# Core_Board.net
KiCad netlist of a schematic drawn in Altium Designer
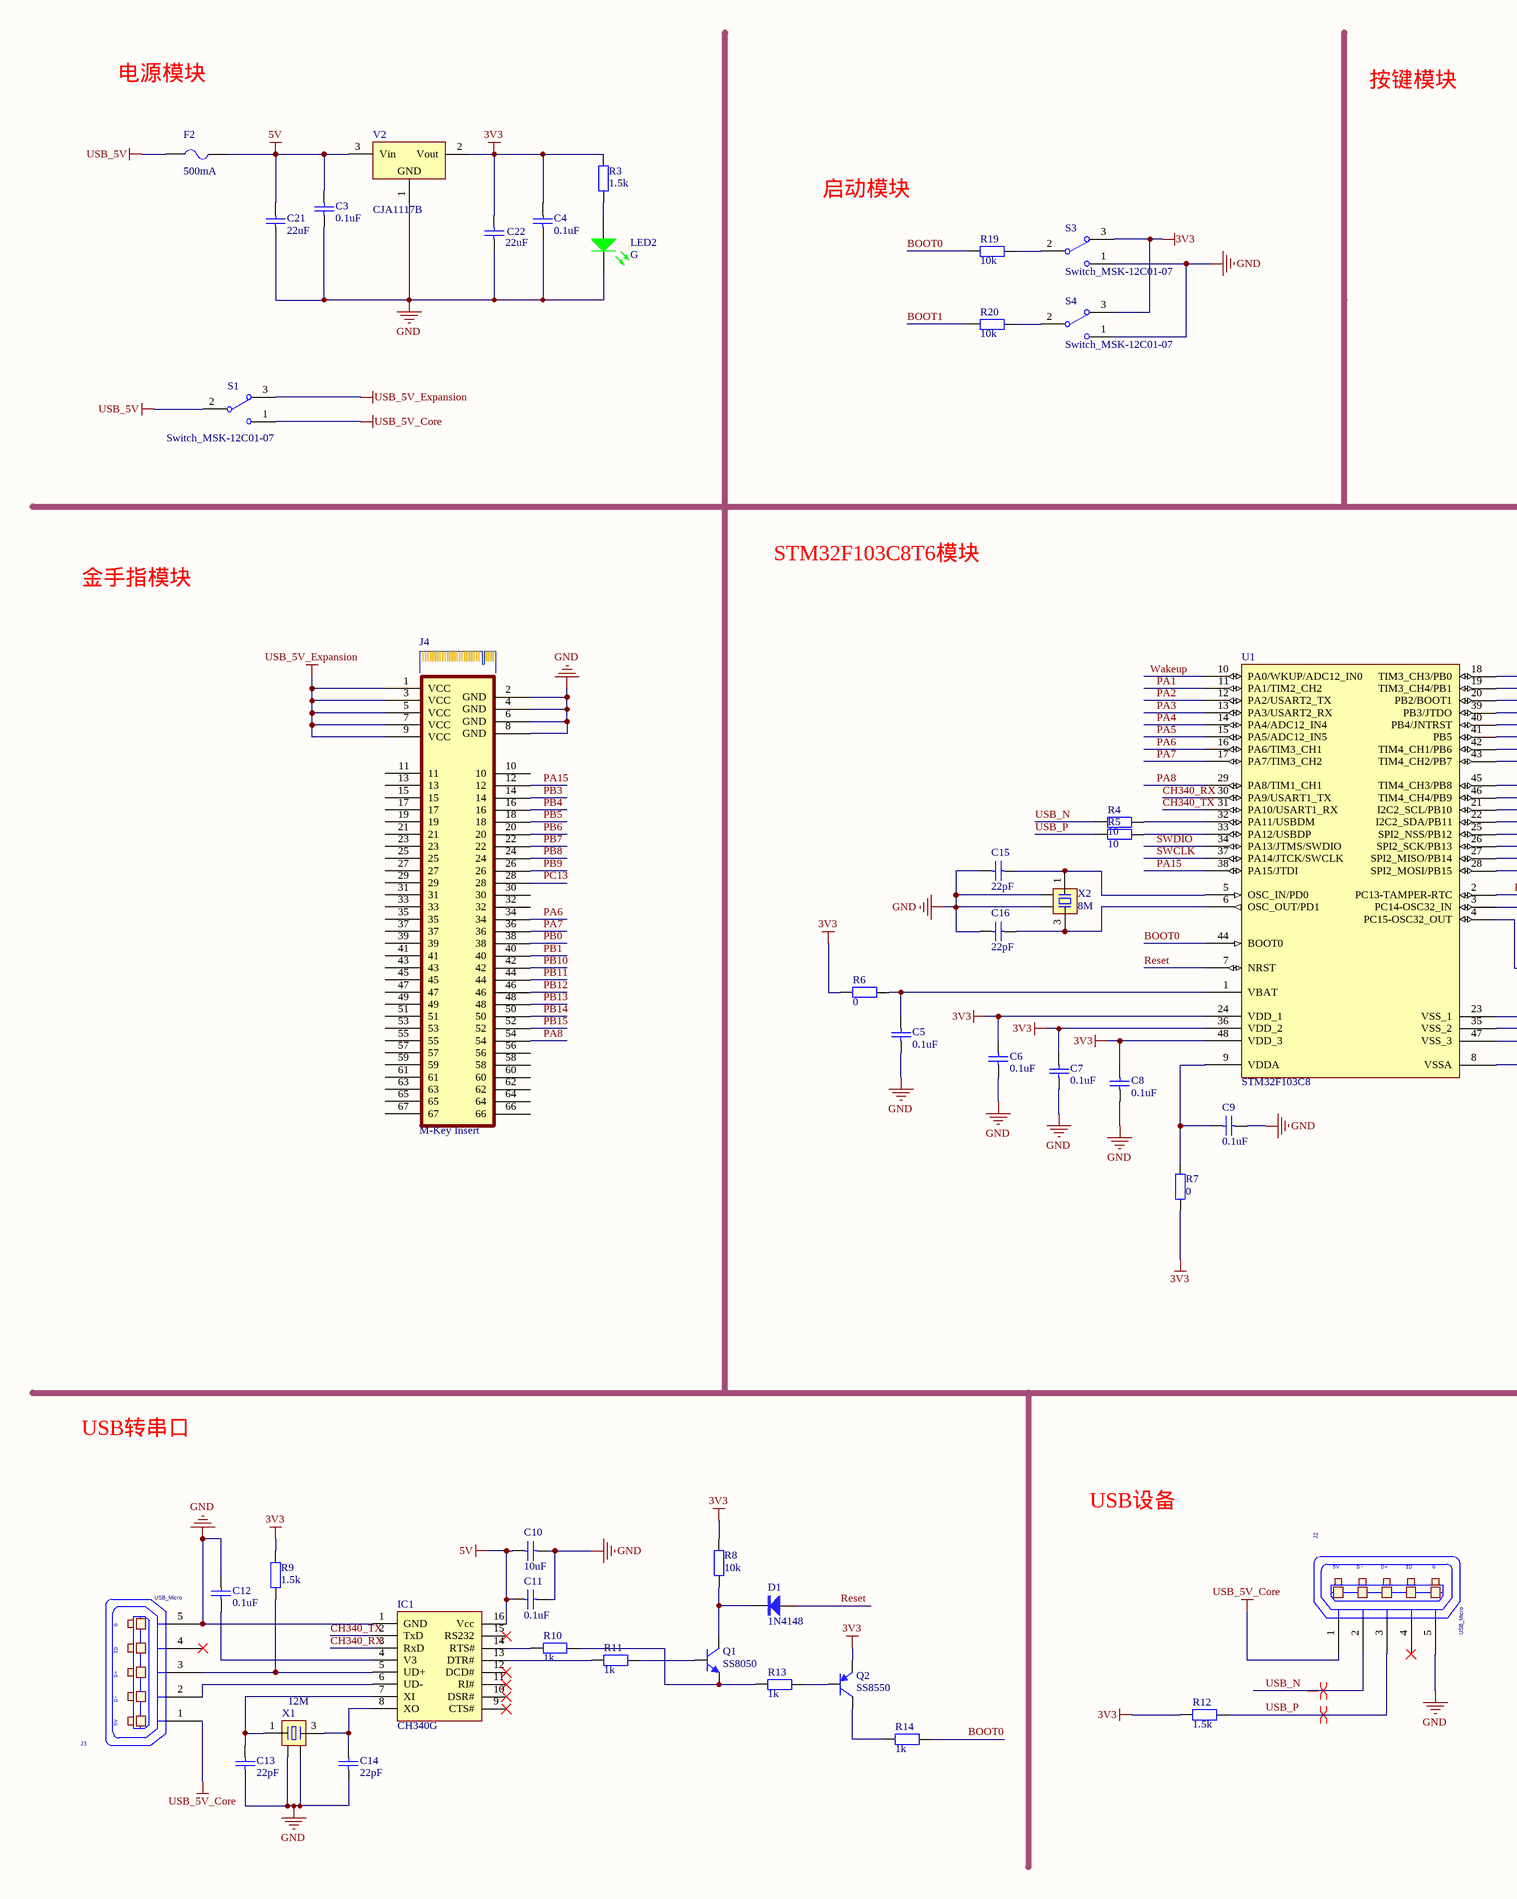
[diagram p0: Core_Board.SchDoc, left]
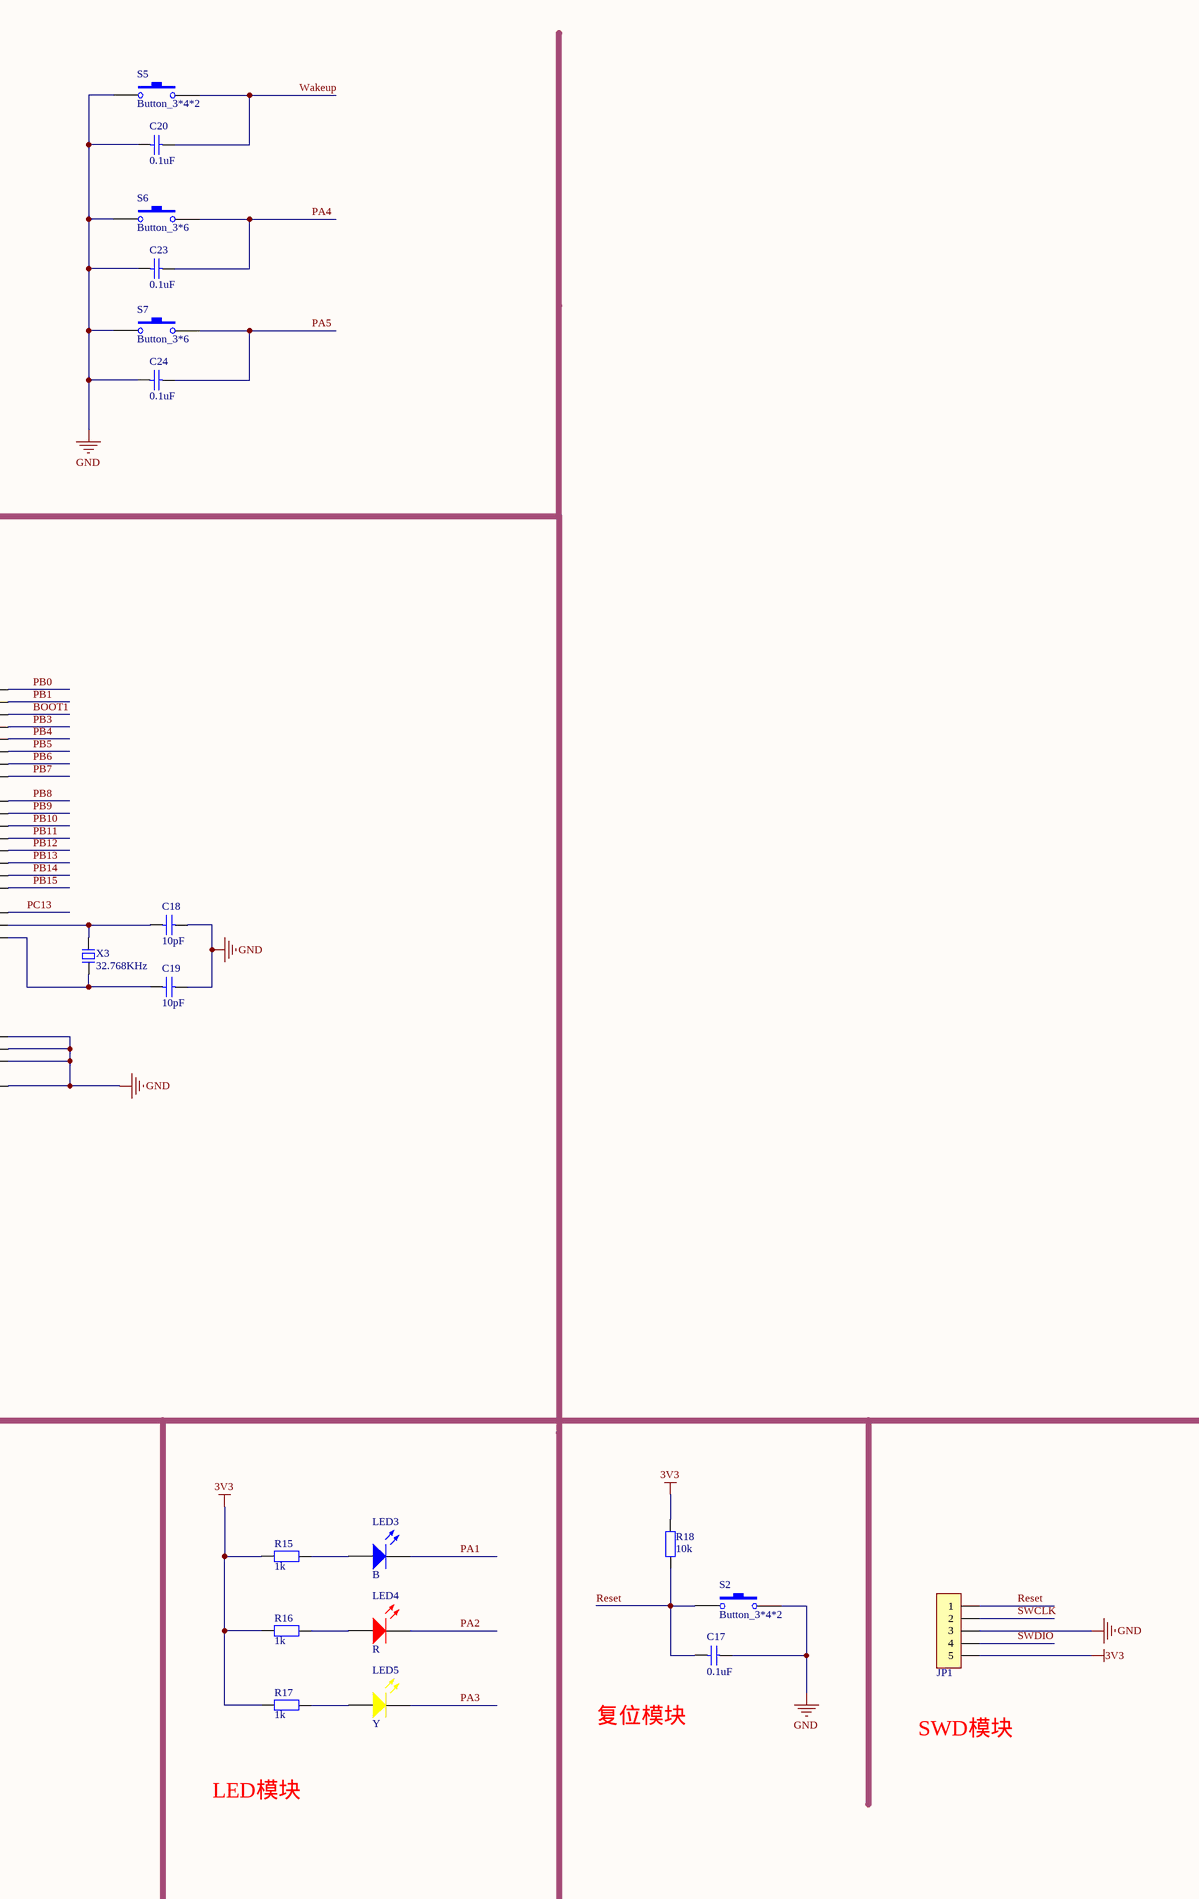
[diagram p1: Core_Board.SchDoc, right]

(export (version "E")
  (design (tool "Eeschema 10.0.6"))
  (components
    (comp (ref "C3")
      (value "0.1uF")
      (footprint "0805_C")
      (description "0805贴片电容")
      (fields (field (name "VOLTAGE") "63V") (field (name "PUBLISHER") "Altium Limited"))
      (libsource (lib "My_Intlib") (part "Cap_SMD"))
    )
    (comp (ref "C4")
      (value "0.1uF")
      (footprint "0805_C")
      (description "0805贴片电容")
      (fields (field (name "VOLTAGE") "63V") (field (name "PUBLISHER") "Altium Limited"))
      (libsource (lib "My_Intlib") (part "Cap_SMD"))
    )
    (comp (ref "C5")
      (value "0.1uF")
      (footprint "0805_C")
      (description "0805贴片电容")
      (fields (field (name "VOLTAGE") "63V") (field (name "PUBLISHER") "Altium Limited"))
      (libsource (lib "My_Intlib") (part "Cap_SMD"))
    )
    (comp (ref "C6")
      (value "0.1uF")
      (footprint "0805_C")
      (description "0805贴片电容")
      (fields (field (name "VOLTAGE") "63V") (field (name "PUBLISHER") "Altium Limited"))
      (libsource (lib "My_Intlib") (part "Cap_SMD"))
    )
    (comp (ref "C7")
      (value "0.1uF")
      (footprint "0805_C")
      (description "0805贴片电容")
      (fields (field (name "VOLTAGE") "63V") (field (name "PUBLISHER") "Altium Limited"))
      (libsource (lib "My_Intlib") (part "Cap_SMD"))
    )
    (comp (ref "C8")
      (value "0.1uF")
      (footprint "0805_C")
      (description "0805贴片电容")
      (fields (field (name "VOLTAGE") "63V") (field (name "PUBLISHER") "Altium Limited"))
      (libsource (lib "My_Intlib") (part "Cap_SMD"))
    )
    (comp (ref "C9")
      (value "0.1uF")
      (footprint "0805_C")
      (description "0805贴片电容")
      (fields (field (name "VOLTAGE") "63V") (field (name "PUBLISHER") "Altium Limited"))
      (libsource (lib "My_Intlib") (part "Cap_SMD"))
    )
    (comp (ref "C10")
      (value "10uF")
      (footprint "0805_C")
      (description "0805贴片电容")
      (fields (field (name "VOLTAGE") "63V") (field (name "PUBLISHER") "Altium Limited"))
      (libsource (lib "My_Intlib") (part "Cap_SMD"))
    )
    (comp (ref "C11")
      (value "0.1uF")
      (footprint "0805_C")
      (description "0805贴片电容")
      (fields (field (name "VOLTAGE") "63V") (field (name "PUBLISHER") "Altium Limited"))
      (libsource (lib "My_Intlib") (part "Cap_SMD"))
    )
    (comp (ref "C12")
      (value "0.1uF")
      (footprint "0805_C")
      (description "0805贴片电容")
      (fields (field (name "VOLTAGE") "63V") (field (name "PUBLISHER") "Altium Limited"))
      (libsource (lib "My_Intlib") (part "Cap_SMD"))
    )
    (comp (ref "C13")
      (value "22pF")
      (footprint "0805_C")
      (description "贴片电容")
      (fields (field (name "VOLTAGE") "63V") (field (name "PUBLISHER") "Altium Limited"))
      (libsource (lib "My_Intlib") (part "Cap_SMD"))
    )
    (comp (ref "C14")
      (value "22pF")
      (footprint "0805_C")
      (description "贴片电容")
      (fields (field (name "VOLTAGE") "63V") (field (name "PUBLISHER") "Altium Limited"))
      (libsource (lib "My_Intlib") (part "Cap_SMD"))
    )
    (comp (ref "C15")
      (value "22pF")
      (footprint "0805_C")
      (description "贴片电容")
      (fields (field (name "VOLTAGE") "63V") (field (name "PUBLISHER") "Altium Limited"))
      (libsource (lib "My_Intlib") (part "Cap_SMD"))
    )
    (comp (ref "C16")
      (value "22pF")
      (footprint "0805_C")
      (description "贴片电容")
      (fields (field (name "VOLTAGE") "63V") (field (name "PUBLISHER") "Altium Limited"))
      (libsource (lib "My_Intlib") (part "Cap_SMD"))
    )
    (comp (ref "C17")
      (value "0.1uF")
      (footprint "0805_C")
      (description "0805贴片电容")
      (fields (field (name "VOLTAGE") "63V") (field (name "PUBLISHER") "Altium Limited"))
      (libsource (lib "My_Intlib") (part "Cap_SMD"))
    )
    (comp (ref "C18")
      (value "10pF")
      (footprint "0805_C")
      (description "贴片电容")
      (fields (field (name "VOLTAGE") "63V") (field (name "PUBLISHER") "Altium Limited"))
      (libsource (lib "My_Intlib") (part "Cap_SMD"))
    )
    (comp (ref "C19")
      (value "10pF")
      (footprint "0805_C")
      (description "贴片电容")
      (fields (field (name "VOLTAGE") "63V") (field (name "PUBLISHER") "Altium Limited"))
      (libsource (lib "My_Intlib") (part "Cap_SMD"))
    )
    (comp (ref "C20")
      (value "0.1uF")
      (footprint "0805_C")
      (description "0805贴片电容")
      (fields (field (name "VOLTAGE") "63V") (field (name "PUBLISHER") "Altium Limited"))
      (libsource (lib "My_Intlib") (part "Cap_SMD"))
    )
    (comp (ref "C21")
      (value "22uF")
      (footprint "0805_C")
      (description "0805贴片电容")
      (fields (field (name "VOLTAGE") "63V") (field (name "PUBLISHER") "Altium Limited"))
      (libsource (lib "My_Intlib") (part "Cap_SMD"))
    )
    (comp (ref "C22")
      (value "22uF")
      (footprint "0805_C")
      (description "0805贴片电容")
      (fields (field (name "VOLTAGE") "63V") (field (name "PUBLISHER") "Altium Limited"))
      (libsource (lib "My_Intlib") (part "Cap_SMD"))
    )
    (comp (ref "C23")
      (value "0.1uF")
      (footprint "0805_C")
      (description "0805贴片电容")
      (fields (field (name "VOLTAGE") "63V") (field (name "PUBLISHER") "Altium Limited"))
      (libsource (lib "My_Intlib") (part "Cap_SMD"))
    )
    (comp (ref "C24")
      (value "0.1uF")
      (footprint "0805_C")
      (description "0805贴片电容")
      (fields (field (name "VOLTAGE") "63V") (field (name "PUBLISHER") "Altium Limited"))
      (libsource (lib "My_Intlib") (part "Cap_SMD"))
    )
    (comp (ref "D1")
      (value "1N4148")
      (footprint "MINI_MELF (LL34)")
      (description "高速开关二极管")
      (fields (field (name "版权归属") "源创客"))
      (libsource (lib "My_Intlib") (part "1N4148"))
    )
    (comp (ref "F2")
      (value "500mA")
      (footprint "FU 1210")
      (description "贴片保险丝")
      (fields (field (name "版权归属") "源创客"))
      (libsource (lib "My_Intlib") (part "FU"))
    )
    (comp (ref "IC1")
      (value "CH340G")
      (footprint "SOP16_N")
      (description "串口转USB")
      (fields (field (name "版权归属") "源创客"))
      (libsource (lib "My_Intlib") (part "CH340G"))
    )
    (comp (ref "J2")
      (value "USB_Micro")
      (footprint "USB-MICRO")
      (libsource (lib "My_Intlib") (part "USB_Micro"))
    )
    (comp (ref "J3")
      (value "USB_Micro")
      (footprint "USB-MICRO")
      (libsource (lib "My_Intlib") (part "USB_Micro"))
    )
    (comp (ref "J4")
      (value "M-Key Insert")
      (footprint "M-Key Insert")
      (description "M.2 金手指")
      (libsource (lib "My_Intlib") (part "M-Key Insert"))
    )
    (comp (ref "JP1")
      (value "HDR-1X5")
      (footprint "XH2.54-WI-5P")
      (description "5P接插件")
      (fields (field (name "版权归属") "源创客"))
      (libsource (lib "My_Intlib") (part "Header 5"))
    )
    (comp (ref "LED2")
      (value "G")
      (footprint "LED 0805G")
      (description "绿色LED")
      (fields (field (name "PUBLISHER") "Altium Limited"))
      (libsource (lib "My_Intlib") (part "LED_G"))
    )
    (comp (ref "LED3")
      (value "B")
      (footprint "LED 0805B")
      (description "蓝色LED")
      (fields (field (name "PUBLISHER") "Altium Limited"))
      (libsource (lib "My_Intlib") (part "LED_B"))
    )
    (comp (ref "LED4")
      (value "R")
      (footprint "LED 0805R")
      (description "红色LED")
      (fields (field (name "PUBLISHER") "Altium Limited"))
      (libsource (lib "My_Intlib") (part "LED_R"))
    )
    (comp (ref "LED5")
      (value "Y")
      (footprint "LED 0805Y")
      (description "黄色LED")
      (fields (field (name "PUBLISHER") "Altium Limited"))
      (libsource (lib "My_Intlib") (part "LED_Y"))
    )
    (comp (ref "Q1")
      (value "SS8050")
      (footprint "SOT23-3N")
      (description "高频放大-NPN型")
      (fields (field (name "版权归属") "源创客"))
      (libsource (lib "My_Intlib") (part "8050-SMD"))
    )
    (comp (ref "Q2")
      (value "SS8550")
      (footprint "SOT23-3N")
      (description "高频放大-PNP型")
      (fields (field (name "版权归属") "源创客"))
      (libsource (lib "My_Intlib") (part "8550-SMD"))
    )
    (comp (ref "R3")
      (value "1.5k")
      (footprint "0805_R")
      (description "0805贴片电阻")
      (fields (field (name "PUBLISHER") "Altium Limited"))
      (libsource (lib "") (part "Res_SMD_1"))
    )
    (comp (ref "R4")
      (value "10")
      (footprint "0805_R")
      (description "0805贴片电阻")
      (fields (field (name "PUBLISHER") "Altium Limited"))
      (libsource (lib "My_Intlib") (part "Res_SMD"))
    )
    (comp (ref "R5")
      (value "10")
      (footprint "0805_R")
      (description "0805贴片电阻")
      (fields (field (name "PUBLISHER") "Altium Limited"))
      (libsource (lib "My_Intlib") (part "Res_SMD"))
    )
    (comp (ref "R6")
      (value "0")
      (footprint "0805_R")
      (description "0805贴片电阻")
      (fields (field (name "PUBLISHER") "Altium Limited"))
      (libsource (lib "My_Intlib") (part "Res_SMD"))
    )
    (comp (ref "R7")
      (value "0")
      (footprint "0805_R")
      (description "0805贴片电阻")
      (fields (field (name "PUBLISHER") "Altium Limited"))
      (libsource (lib "") (part "Res_SMD_1"))
    )
    (comp (ref "R8")
      (value "10k")
      (footprint "0805_R")
      (description "0805贴片电阻")
      (fields (field (name "PUBLISHER") "Altium Limited"))
      (libsource (lib "") (part "Res_SMD_1"))
    )
    (comp (ref "R9")
      (value "1.5k")
      (footprint "0805_R")
      (description "0805贴片电阻")
      (fields (field (name "PUBLISHER") "Altium Limited"))
      (libsource (lib "") (part "Res_SMD_2"))
    )
    (comp (ref "R10")
      (value "1k")
      (footprint "0805_R")
      (description "0805贴片电阻")
      (fields (field (name "PUBLISHER") "Altium Limited"))
      (libsource (lib "My_Intlib") (part "Res_SMD"))
    )
    (comp (ref "R11")
      (value "1k")
      (footprint "0805_R")
      (description "0805贴片电阻")
      (fields (field (name "PUBLISHER") "Altium Limited"))
      (libsource (lib "My_Intlib") (part "Res_SMD"))
    )
    (comp (ref "R12")
      (value "1.5k")
      (footprint "0805_R")
      (description "0805贴片电阻")
      (fields (field (name "PUBLISHER") "Altium Limited"))
      (libsource (lib "My_Intlib") (part "Res_SMD"))
    )
    (comp (ref "R13")
      (value "1k")
      (footprint "0805_R")
      (description "0805贴片电阻")
      (fields (field (name "PUBLISHER") "Altium Limited"))
      (libsource (lib "My_Intlib") (part "Res_SMD"))
    )
    (comp (ref "R14")
      (value "1k")
      (footprint "0805_R")
      (description "0805贴片电阻")
      (fields (field (name "PUBLISHER") "Altium Limited"))
      (libsource (lib "") (part "Res_SMD_3"))
    )
    (comp (ref "R15")
      (value "1k")
      (footprint "0805_R")
      (description "0805贴片电阻")
      (fields (field (name "PUBLISHER") "Altium Limited"))
      (libsource (lib "My_Intlib") (part "Res_SMD"))
    )
    (comp (ref "R16")
      (value "1k")
      (footprint "0805_R")
      (description "0805贴片电阻")
      (fields (field (name "PUBLISHER") "Altium Limited"))
      (libsource (lib "My_Intlib") (part "Res_SMD"))
    )
    (comp (ref "R17")
      (value "1k")
      (footprint "0805_R")
      (description "0805贴片电阻")
      (fields (field (name "PUBLISHER") "Altium Limited"))
      (libsource (lib "My_Intlib") (part "Res_SMD"))
    )
    (comp (ref "R18")
      (value "10k")
      (footprint "0805_R")
      (description "0805贴片电阻")
      (fields (field (name "PUBLISHER") "Altium Limited"))
      (libsource (lib "") (part "Res_SMD_2"))
    )
    (comp (ref "R19")
      (value "10k")
      (footprint "0805_R")
      (description "0805贴片电阻")
      (fields (field (name "PUBLISHER") "Altium Limited"))
      (libsource (lib "My_Intlib") (part "Res_SMD"))
    )
    (comp (ref "R20")
      (value "10k")
      (footprint "0805_R")
      (description "0805贴片电阻")
      (fields (field (name "PUBLISHER") "Altium Limited"))
      (libsource (lib "My_Intlib") (part "Res_SMD"))
    )
    (comp (ref "S1")
      (value "Switch_MSK-12C01-07")
      (footprint "MSK-12C01-07")
      (libsource (lib "My_Intlib") (part "Switch_MSK-12C01-07"))
    )
    (comp (ref "S2")
      (value "Button_3*4*2")
      (footprint "TSW SMD-3*4*2")
      (fields (field (name "PUBLISHER") "Altium Limited"))
      (libsource (lib "My_Intlib") (part "Button_3*4*2"))
    )
    (comp (ref "S3")
      (value "Switch_MSK-12C01-07")
      (footprint "MSK-12C01-07")
      (libsource (lib "My_Intlib") (part "Switch_MSK-12C01-07"))
    )
    (comp (ref "S4")
      (value "Switch_MSK-12C01-07")
      (footprint "MSK-12C01-07")
      (libsource (lib "My_Intlib") (part "Switch_MSK-12C01-07"))
    )
    (comp (ref "S5")
      (value "Button_3*4*2")
      (footprint "TSW SMD-3*4*2")
      (fields (field (name "PUBLISHER") "Altium Limited"))
      (libsource (lib "My_Intlib") (part "Button_3*4*2"))
    )
    (comp (ref "S6")
      (value "Button_3*6")
      (footprint "TSW SMD-3*6*4.3_V")
      (description "3mm*4mm*按钮长度待定")
      (fields (field (name "PUBLISHER") "Altium Limited"))
      (libsource (lib "My_Intlib") (part "Button_3*6"))
    )
    (comp (ref "S7")
      (value "Button_3*6")
      (footprint "TSW SMD-3*6*4.3_V")
      (description "3mm*4mm*按钮长度待定")
      (fields (field (name "PUBLISHER") "Altium Limited"))
      (libsource (lib "My_Intlib") (part "Button_3*6"))
    )
    (comp (ref "U1")
      (value "STM32F103C8")
      (footprint "LQFP48 7X7_N")
      (description "Flaah:64/RAM:20/IO:36")
      (libsource (lib "My_Intlib") (part "STM32F103C8"))
    )
    (comp (ref "V2")
      (value "CJA1117B")
      (footprint "SOT89_N")
      (description "三端稳压芯片")
      (fields (field (name "版权归属") "源创客"))
      (libsource (lib "My_Intlib") (part "CJA1117B"))
    )
    (comp (ref "X1")
      (value "12M")
      (footprint "OSC 3225-4P")
      (description "4脚无源晶振")
      (fields (field (name "版权归属") "源创客"))
      (libsource (lib "My_Intlib") (part "XTAL-4P"))
    )
    (comp (ref "X2")
      (value "8M")
      (footprint "OSC 3225-4P")
      (description "4脚无源晶振")
      (fields (field (name "版权归属") "源创客"))
      (libsource (lib "") (part "XTAL-4P_1"))
    )
    (comp (ref "X3")
      (value "32.768KHz")
      (footprint "OSC 3215-2P")
      (description "2脚无源脚晶振")
      (fields (field (name "版权归属") "源创客"))
      (libsource (lib "10.1 - 保险丝-晶振") (part "XTAL-2P"))
    )
  )
  (nets
    (net (code "1") (name "/BOOT0") (class "Default")
      (node (ref "R14") (pin "1") (pinfunction "1_1") (pintype "passive"))
      (node (ref "R19") (pin "1") (pinfunction "1_1") (pintype "passive"))
      (node (ref "U1") (pin "44") (pinfunction "BOOT0_44") (pintype "input"))
    )
    (net (code "2") (name "/BOOT1") (class "Default")
      (node (ref "R20") (pin "1") (pinfunction "1_1") (pintype "passive"))
      (node (ref "U1") (pin "20") (pinfunction "PB2/BOOT1_20") (pintype "bidirectional"))
    )
    (net (code "3") (name "/CH340_RX") (class "Default")
      (node (ref "IC1") (pin "3") (pinfunction "RxD_3") (pintype "passive"))
      (node (ref "U1") (pin "30") (pinfunction "PA9/USART1_TX_30") (pintype "bidirectional"))
    )
    (net (code "4") (name "/CH340_TX") (class "Default")
      (node (ref "IC1") (pin "2") (pinfunction "TxD_2") (pintype "passive"))
      (node (ref "U1") (pin "31") (pinfunction "PA10/USART1_RX_31") (pintype "bidirectional"))
    )
    (net (code "5") (name "/PA1") (class "Default")
      (node (ref "LED3") (pin "2") (pinfunction "K_2") (pintype "passive"))
      (node (ref "U1") (pin "11") (pinfunction "PA1/TIM2_CH2_11") (pintype "bidirectional"))
    )
    (net (code "6") (name "/PA2") (class "Default")
      (node (ref "LED4") (pin "2") (pinfunction "K_2") (pintype "passive"))
      (node (ref "U1") (pin "12") (pinfunction "PA2/USART2_TX_12") (pintype "bidirectional"))
    )
    (net (code "7") (name "/PA3") (class "Default")
      (node (ref "LED5") (pin "2") (pinfunction "K_2") (pintype "passive"))
      (node (ref "U1") (pin "13") (pinfunction "PA3/USART2_RX_13") (pintype "bidirectional"))
    )
    (net (code "8") (name "/PA4") (class "Default")
      (node (ref "C23") (pin "2") (pinfunction "2_2") (pintype "passive"))
      (node (ref "S6") (pin "2") (pinfunction "2_2") (pintype "passive"))
      (node (ref "U1") (pin "14") (pinfunction "PA4/ADC12_IN4_14") (pintype "bidirectional"))
    )
    (net (code "9") (name "/PA5") (class "Default")
      (node (ref "C24") (pin "2") (pinfunction "2_2") (pintype "passive"))
      (node (ref "S7") (pin "2") (pinfunction "2_2") (pintype "passive"))
      (node (ref "U1") (pin "15") (pinfunction "PA5/ADC12_IN5_15") (pintype "bidirectional"))
    )
    (net (code "10") (name "/PA6") (class "Default")
      (node (ref "J4") (pin "34") (pinfunction "34_34") (pintype "passive"))
      (node (ref "U1") (pin "16") (pinfunction "PA6/TIM3_CH1_16") (pintype "bidirectional"))
    )
    (net (code "11") (name "/PA7") (class "Default")
      (node (ref "J4") (pin "36") (pinfunction "36_36") (pintype "passive"))
      (node (ref "U1") (pin "17") (pinfunction "PA7/TIM3_CH2_17") (pintype "bidirectional"))
    )
    (net (code "12") (name "/PA8") (class "Default")
      (node (ref "J4") (pin "54") (pinfunction "54_54") (pintype "passive"))
      (node (ref "U1") (pin "29") (pinfunction "PA8/TIM1_CH1_29") (pintype "bidirectional"))
    )
    (net (code "13") (name "/PA15") (class "Default")
      (node (ref "J4") (pin "12") (pinfunction "12_12") (pintype "passive"))
      (node (ref "U1") (pin "38") (pinfunction "PA15/JTDI_38") (pintype "bidirectional"))
    )
    (net (code "14") (name "/PB0") (class "Default")
      (node (ref "J4") (pin "38") (pinfunction "38_38") (pintype "passive"))
      (node (ref "U1") (pin "18") (pinfunction "TIM3_CH3/PB0_18") (pintype "bidirectional"))
    )
    (net (code "15") (name "/PB1") (class "Default")
      (node (ref "J4") (pin "40") (pinfunction "40_40") (pintype "passive"))
      (node (ref "U1") (pin "19") (pinfunction "TIM3_CH4/PB1_19") (pintype "bidirectional"))
    )
    (net (code "16") (name "/PB3") (class "Default")
      (node (ref "J4") (pin "14") (pinfunction "14_14") (pintype "passive"))
      (node (ref "U1") (pin "39") (pinfunction "PB3/JTDO_39") (pintype "bidirectional"))
    )
    (net (code "17") (name "/PB4") (class "Default")
      (node (ref "J4") (pin "16") (pinfunction "16_16") (pintype "passive"))
      (node (ref "U1") (pin "40") (pinfunction "PB4/JNTRST_40") (pintype "bidirectional"))
    )
    (net (code "18") (name "/PB5") (class "Default")
      (node (ref "J4") (pin "18") (pinfunction "18_18") (pintype "passive"))
      (node (ref "U1") (pin "41") (pinfunction "PB5_41") (pintype "bidirectional"))
    )
    (net (code "19") (name "/PB6") (class "Default")
      (node (ref "J4") (pin "20") (pinfunction "20_20") (pintype "passive"))
      (node (ref "U1") (pin "42") (pinfunction "TIM4_CH1/PB6_42") (pintype "bidirectional"))
    )
    (net (code "20") (name "/PB7") (class "Default")
      (node (ref "J4") (pin "22") (pinfunction "22_22") (pintype "passive"))
      (node (ref "U1") (pin "43") (pinfunction "TIM4_CH2/PB7_43") (pintype "bidirectional"))
    )
    (net (code "21") (name "/PB8") (class "Default")
      (node (ref "J4") (pin "24") (pinfunction "24_24") (pintype "passive"))
      (node (ref "U1") (pin "45") (pinfunction "TIM4_CH3/PB8_45") (pintype "bidirectional"))
    )
    (net (code "22") (name "/PB9") (class "Default")
      (node (ref "J4") (pin "26") (pinfunction "26_26") (pintype "passive"))
      (node (ref "U1") (pin "46") (pinfunction "TIM4_CH4/PB9_46") (pintype "bidirectional"))
    )
    (net (code "23") (name "/PB10") (class "Default")
      (node (ref "J4") (pin "42") (pinfunction "42_42") (pintype "passive"))
      (node (ref "U1") (pin "21") (pinfunction "I2C2_SCL/PB10_21") (pintype "bidirectional"))
    )
    (net (code "24") (name "/PB11") (class "Default")
      (node (ref "J4") (pin "44") (pinfunction "44_44") (pintype "passive"))
      (node (ref "U1") (pin "22") (pinfunction "I2C2_SDA/PB11_22") (pintype "bidirectional"))
    )
    (net (code "25") (name "/PB12") (class "Default")
      (node (ref "J4") (pin "46") (pinfunction "46_46") (pintype "passive"))
      (node (ref "U1") (pin "25") (pinfunction "SPI2_NSS/PB12_25") (pintype "bidirectional"))
    )
    (net (code "26") (name "/PB13") (class "Default")
      (node (ref "J4") (pin "48") (pinfunction "48_48") (pintype "passive"))
      (node (ref "U1") (pin "26") (pinfunction "SPI2_SCK/PB13_26") (pintype "bidirectional"))
    )
    (net (code "27") (name "/PB14") (class "Default")
      (node (ref "J4") (pin "50") (pinfunction "50_50") (pintype "passive"))
      (node (ref "U1") (pin "27") (pinfunction "SPI2_MISO/PB14_27") (pintype "bidirectional"))
    )
    (net (code "28") (name "/PB15") (class "Default")
      (node (ref "J4") (pin "52") (pinfunction "52_52") (pintype "passive"))
      (node (ref "U1") (pin "28") (pinfunction "SPI2_MOSI/PB15_28") (pintype "bidirectional"))
    )
    (net (code "29") (name "/PC13") (class "Default")
      (node (ref "J4") (pin "28") (pinfunction "28_28") (pintype "passive"))
      (node (ref "U1") (pin "2") (pinfunction "PC13-TAMPER-RTC_2") (pintype "bidirectional"))
    )
    (net (code "30") (name "/Reset") (class "Default")
      (node (ref "C17") (pin "2") (pinfunction "2_2") (pintype "passive"))
      (node (ref "D1") (pin "1") (pinfunction "A_1") (pintype "passive"))
      (node (ref "JP1") (pin "1") (pinfunction "1_1") (pintype "passive"))
      (node (ref "R18") (pin "2") (pinfunction "2_2") (pintype "passive"))
      (node (ref "S2") (pin "1") (pinfunction "1_1") (pintype "passive"))
      (node (ref "U1") (pin "7") (pinfunction "NRST_7") (pintype "bidirectional"))
    )
    (net (code "31") (name "/SWCLK") (class "Default")
      (node (ref "JP1") (pin "2") (pinfunction "2_2") (pintype "passive"))
      (node (ref "U1") (pin "37") (pinfunction "PA14/JTCK/SWCLK_37") (pintype "bidirectional"))
    )
    (net (code "32") (name "/SWDIO") (class "Default")
      (node (ref "JP1") (pin "4") (pinfunction "4_4") (pintype "passive"))
      (node (ref "U1") (pin "34") (pinfunction "PA13/JTMS/SWDIO_34") (pintype "bidirectional"))
    )
    (net (code "33") (name "/USB_N") (class "Default")
      (node (ref "J2") (pin "2") (pinfunction "P2_2") (pintype "passive"))
      (node (ref "R4") (pin "1") (pinfunction "1_1") (pintype "passive"))
    )
    (net (code "34") (name "/USB_P") (class "Default")
      (node (ref "J2") (pin "3") (pinfunction "P3_3") (pintype "passive"))
      (node (ref "R12") (pin "2") (pinfunction "2_2") (pintype "passive"))
      (node (ref "R5") (pin "1") (pinfunction "1_1") (pintype "passive"))
    )
    (net (code "35") (name "/Wakeup") (class "Default")
      (node (ref "C20") (pin "2") (pinfunction "2_2") (pintype "passive"))
      (node (ref "S5") (pin "2") (pinfunction "2_2") (pintype "passive"))
      (node (ref "U1") (pin "10") (pinfunction "PA0/WKUP/ADC12_IN0_10") (pintype "bidirectional"))
    )
    (net (code "36") (name "3V3") (class "Default")
      (node (ref "C22") (pin "2") (pinfunction "2_2") (pintype "passive"))
      (node (ref "C4") (pin "2") (pinfunction "2_2") (pintype "passive"))
      (node (ref "C6") (pin "2") (pinfunction "2_2") (pintype "passive"))
      (node (ref "C7") (pin "2") (pinfunction "2_2") (pintype "passive"))
      (node (ref "C8") (pin "2") (pinfunction "2_2") (pintype "passive"))
      (node (ref "JP1") (pin "5") (pinfunction "5_5") (pintype "passive"))
      (node (ref "Q2") (pin "2") (pinfunction "E_2") (pintype "passive"))
      (node (ref "R12") (pin "1") (pinfunction "1_1") (pintype "passive"))
      (node (ref "R15") (pin "1") (pinfunction "1_1") (pintype "passive"))
      (node (ref "R16") (pin "1") (pinfunction "1_1") (pintype "passive"))
      (node (ref "R17") (pin "1") (pinfunction "1_1") (pintype "passive"))
      (node (ref "R18") (pin "1") (pinfunction "1_1") (pintype "passive"))
      (node (ref "R3") (pin "2") (pinfunction "2_2") (pintype "passive"))
      (node (ref "R6") (pin "1") (pinfunction "1_1") (pintype "passive"))
      (node (ref "R7") (pin "1") (pinfunction "1_1") (pintype "passive"))
      (node (ref "R8") (pin "2") (pinfunction "2_2") (pintype "passive"))
      (node (ref "R9") (pin "1") (pinfunction "1_1") (pintype "passive"))
      (node (ref "S3") (pin "3") (pinfunction "3_3") (pintype "passive"))
      (node (ref "S4") (pin "3") (pinfunction "3_3") (pintype "passive"))
      (node (ref "U1") (pin "24") (pinfunction "VDD_1_24") (pintype "power_in"))
      (node (ref "U1") (pin "36") (pinfunction "VDD_2_36") (pintype "power_in"))
      (node (ref "U1") (pin "48") (pinfunction "VDD_3_48") (pintype "power_in"))
      (node (ref "V2") (pin "2") (pinfunction "Vout_2") (pintype "passive"))
    )
    (net (code "37") (name "5V") (class "Default")
      (node (ref "C10") (pin "2") (pinfunction "2_2") (pintype "passive"))
      (node (ref "C11") (pin "2") (pinfunction "2_2") (pintype "passive"))
      (node (ref "C21") (pin "2") (pinfunction "2_2") (pintype "passive"))
      (node (ref "C3") (pin "2") (pinfunction "2_2") (pintype "passive"))
      (node (ref "F2") (pin "2") (pinfunction "2_2") (pintype "passive"))
      (node (ref "IC1") (pin "16") (pinfunction "Vcc_16") (pintype "passive"))
      (node (ref "V2") (pin "3") (pinfunction "Vin_3") (pintype "passive"))
    )
    (net (code "38") (name "GND") (class "Default")
      (node (ref "C10") (pin "1") (pinfunction "1_1") (pintype "passive"))
      (node (ref "C11") (pin "1") (pinfunction "1_1") (pintype "passive"))
      (node (ref "C12") (pin "2") (pinfunction "2_2") (pintype "passive"))
      (node (ref "C13") (pin "1") (pinfunction "1_1") (pintype "passive"))
      (node (ref "C14") (pin "1") (pinfunction "1_1") (pintype "passive"))
      (node (ref "C15") (pin "2") (pinfunction "2_2") (pintype "passive"))
      (node (ref "C16") (pin "2") (pinfunction "2_2") (pintype "passive"))
      (node (ref "C17") (pin "1") (pinfunction "1_1") (pintype "passive"))
      (node (ref "C18") (pin "2") (pinfunction "2_2") (pintype "passive"))
      (node (ref "C19") (pin "2") (pinfunction "2_2") (pintype "passive"))
      (node (ref "C20") (pin "1") (pinfunction "1_1") (pintype "passive"))
      (node (ref "C21") (pin "1") (pinfunction "1_1") (pintype "passive"))
      (node (ref "C22") (pin "1") (pinfunction "1_1") (pintype "passive"))
      (node (ref "C23") (pin "1") (pinfunction "1_1") (pintype "passive"))
      (node (ref "C24") (pin "1") (pinfunction "1_1") (pintype "passive"))
      (node (ref "C3") (pin "1") (pinfunction "1_1") (pintype "passive"))
      (node (ref "C4") (pin "1") (pinfunction "1_1") (pintype "passive"))
      (node (ref "C5") (pin "1") (pinfunction "1_1") (pintype "passive"))
      (node (ref "C6") (pin "1") (pinfunction "1_1") (pintype "passive"))
      (node (ref "C7") (pin "1") (pinfunction "1_1") (pintype "passive"))
      (node (ref "C8") (pin "1") (pinfunction "1_1") (pintype "passive"))
      (node (ref "C9") (pin "1") (pinfunction "1_1") (pintype "passive"))
      (node (ref "IC1") (pin "1") (pinfunction "GND_1") (pintype "passive"))
      (node (ref "J2") (pin "5") (pinfunction "P5_5") (pintype "passive"))
      (node (ref "J3") (pin "5") (pinfunction "P5_5") (pintype "passive"))
      (node (ref "J4") (pin "2") (pinfunction "GND_2") (pintype "passive"))
      (node (ref "J4") (pin "4") (pinfunction "GND_4") (pintype "passive"))
      (node (ref "J4") (pin "6") (pinfunction "GND_6") (pintype "passive"))
      (node (ref "J4") (pin "8") (pinfunction "GND_8") (pintype "passive"))
      (node (ref "JP1") (pin "3") (pinfunction "3_3") (pintype "passive"))
      (node (ref "LED2") (pin "2") (pinfunction "K_2") (pintype "passive"))
      (node (ref "S2") (pin "2") (pinfunction "2_2") (pintype "passive"))
      (node (ref "S3") (pin "1") (pinfunction "1_1") (pintype "passive"))
      (node (ref "S4") (pin "1") (pinfunction "1_1") (pintype "passive"))
      (node (ref "S5") (pin "1") (pinfunction "1_1") (pintype "passive"))
      (node (ref "S6") (pin "1") (pinfunction "1_1") (pintype "passive"))
      (node (ref "S7") (pin "1") (pinfunction "1_1") (pintype "passive"))
      (node (ref "U1") (pin "23") (pinfunction "VSS_1_23") (pintype "power_in"))
      (node (ref "U1") (pin "35") (pinfunction "VSS_2_35") (pintype "power_in"))
      (node (ref "U1") (pin "47") (pinfunction "VSS_3_47") (pintype "power_in"))
      (node (ref "U1") (pin "8") (pinfunction "VSSA_8") (pintype "power_in"))
      (node (ref "V2") (pin "1") (pinfunction "GND_1") (pintype "passive"))
      (node (ref "X1") (pin "2") (pinfunction "2_2") (pintype "passive"))
      (node (ref "X1") (pin "4") (pinfunction "4_4") (pintype "passive"))
      (node (ref "X2") (pin "2") (pinfunction "2_2") (pintype "passive"))
      (node (ref "X2") (pin "4") (pinfunction "4_4") (pintype "passive"))
    )
    (net (code "39") (name "Net-(D1-K)") (class "Default")
      (node (ref "D1") (pin "2") (pinfunction "K_2") (pintype "passive"))
      (node (ref "Q1") (pin "3") (pinfunction "C_3") (pintype "passive"))
      (node (ref "R8") (pin "1") (pinfunction "1_1") (pintype "passive"))
    )
    (net (code "40") (name "Net-(IC1-DTR#)") (class "Default")
      (node (ref "IC1") (pin "13") (pinfunction "DTR#_13") (pintype "passive"))
      (node (ref "R11") (pin "1") (pinfunction "1_1") (pintype "passive"))
    )
    (net (code "41") (name "Net-(IC1-RTS#)") (class "Default")
      (node (ref "IC1") (pin "14") (pinfunction "RTS#_14") (pintype "passive"))
      (node (ref "R10") (pin "1") (pinfunction "1_1") (pintype "passive"))
    )
    (net (code "42") (name "Net-(IC1-UD+)") (class "Default")
      (node (ref "IC1") (pin "5") (pinfunction "UD+_5") (pintype "passive"))
      (node (ref "J3") (pin "3") (pinfunction "P3_3") (pintype "passive"))
      (node (ref "R9") (pin "2") (pinfunction "2_2") (pintype "passive"))
    )
    (net (code "43") (name "Net-(IC1-UD-)") (class "Default")
      (node (ref "IC1") (pin "6") (pinfunction "UD-_6") (pintype "passive"))
      (node (ref "J3") (pin "2") (pinfunction "P2_2") (pintype "passive"))
    )
    (net (code "44") (name "Net-(IC1-V3)") (class "Default")
      (node (ref "C12") (pin "1") (pinfunction "1_1") (pintype "passive"))
      (node (ref "IC1") (pin "4") (pinfunction "V3_4") (pintype "passive"))
    )
    (net (code "45") (name "Net-(IC1-XI)") (class "Default")
      (node (ref "C13") (pin "2") (pinfunction "2_2") (pintype "passive"))
      (node (ref "IC1") (pin "7") (pinfunction "XI_7") (pintype "passive"))
      (node (ref "X1") (pin "1") (pinfunction "1_1") (pintype "passive"))
    )
    (net (code "46") (name "Net-(IC1-XO)") (class "Default")
      (node (ref "C14") (pin "2") (pinfunction "2_2") (pintype "passive"))
      (node (ref "IC1") (pin "8") (pinfunction "XO_8") (pintype "passive"))
      (node (ref "X1") (pin "3") (pinfunction "3_3") (pintype "passive"))
    )
    (net (code "47") (name "Net-(LED2-A)") (class "Default")
      (node (ref "LED2") (pin "1") (pinfunction "A_1") (pintype "passive"))
      (node (ref "R3") (pin "1") (pinfunction "1_1") (pintype "passive"))
    )
    (net (code "48") (name "Net-(LED3-A)") (class "Default")
      (node (ref "LED3") (pin "1") (pinfunction "A_1") (pintype "passive"))
      (node (ref "R15") (pin "2") (pinfunction "2_2") (pintype "passive"))
    )
    (net (code "49") (name "Net-(LED4-A)") (class "Default")
      (node (ref "LED4") (pin "1") (pinfunction "A_1") (pintype "passive"))
      (node (ref "R16") (pin "2") (pinfunction "2_2") (pintype "passive"))
    )
    (net (code "50") (name "Net-(LED5-A)") (class "Default")
      (node (ref "LED5") (pin "1") (pinfunction "A_1") (pintype "passive"))
      (node (ref "R17") (pin "2") (pinfunction "2_2") (pintype "passive"))
    )
    (net (code "51") (name "Net-(Q1-B)") (class "Default")
      (node (ref "Q1") (pin "1") (pinfunction "B_1") (pintype "passive"))
      (node (ref "R11") (pin "2") (pinfunction "2_2") (pintype "passive"))
    )
    (net (code "52") (name "Net-(Q1-E)") (class "Default")
      (node (ref "Q1") (pin "2") (pinfunction "E_2") (pintype "passive"))
      (node (ref "R10") (pin "2") (pinfunction "2_2") (pintype "passive"))
      (node (ref "R13") (pin "1") (pinfunction "1_1") (pintype "passive"))
    )
    (net (code "53") (name "Net-(Q2-B)") (class "Default")
      (node (ref "Q2") (pin "1") (pinfunction "B_1") (pintype "passive"))
      (node (ref "R13") (pin "2") (pinfunction "2_2") (pintype "passive"))
    )
    (net (code "54") (name "Net-(Q2-C)") (class "Default")
      (node (ref "Q2") (pin "3") (pinfunction "C_3") (pintype "passive"))
      (node (ref "R14") (pin "2") (pinfunction "2_2") (pintype "passive"))
    )
    (net (code "55") (name "Net-(R19-Pad2)") (class "Default")
      (node (ref "R19") (pin "2") (pinfunction "2_2") (pintype "passive"))
      (node (ref "S3") (pin "2") (pinfunction "2_2") (pintype "passive"))
    )
    (net (code "56") (name "Net-(R20-Pad2)") (class "Default")
      (node (ref "R20") (pin "2") (pinfunction "2_2") (pintype "passive"))
      (node (ref "S4") (pin "2") (pinfunction "2_2") (pintype "passive"))
    )
    (net (code "57") (name "Net-(U1-OSC_IN{slash}PD0)") (class "Default")
      (node (ref "C15") (pin "1") (pinfunction "1_1") (pintype "passive"))
      (node (ref "U1") (pin "5") (pinfunction "OSC_IN/PD0_5") (pintype "input"))
      (node (ref "X2") (pin "1") (pinfunction "1_1") (pintype "passive"))
    )
    (net (code "58") (name "Net-(U1-OSC_OUT{slash}PD1)") (class "Default")
      (node (ref "C16") (pin "1") (pinfunction "1_1") (pintype "passive"))
      (node (ref "U1") (pin "6") (pinfunction "OSC_OUT/PD1_6") (pintype "output"))
      (node (ref "X2") (pin "3") (pinfunction "3_3") (pintype "passive"))
    )
    (net (code "59") (name "Net-(U1-PA11{slash}USBDM)") (class "Default")
      (node (ref "R4") (pin "2") (pinfunction "2_2") (pintype "passive"))
      (node (ref "U1") (pin "32") (pinfunction "PA11/USBDM_32") (pintype "bidirectional"))
    )
    (net (code "60") (name "Net-(U1-PA12{slash}USBDP)") (class "Default")
      (node (ref "R5") (pin "2") (pinfunction "2_2") (pintype "passive"))
      (node (ref "U1") (pin "33") (pinfunction "PA12/USBDP_33") (pintype "bidirectional"))
    )
    (net (code "61") (name "Net-(U1-PC14-OSC32_IN)") (class "Default")
      (node (ref "C18") (pin "1") (pinfunction "1_1") (pintype "passive"))
      (node (ref "U1") (pin "3") (pinfunction "PC14-OSC32_IN_3") (pintype "bidirectional"))
      (node (ref "X3") (pin "2") (pinfunction "2_2") (pintype "passive"))
    )
    (net (code "62") (name "Net-(U1-PC15-OSC32_OUT)") (class "Default")
      (node (ref "C19") (pin "1") (pinfunction "1_1") (pintype "passive"))
      (node (ref "U1") (pin "4") (pinfunction "PC15-OSC32_OUT_4") (pintype "bidirectional"))
      (node (ref "X3") (pin "1") (pinfunction "1_1") (pintype "passive"))
    )
    (net (code "63") (name "Net-(U1-VBAT)") (class "Default")
      (node (ref "C5") (pin "2") (pinfunction "2_2") (pintype "passive"))
      (node (ref "R6") (pin "2") (pinfunction "2_2") (pintype "passive"))
      (node (ref "U1") (pin "1") (pinfunction "VBAT_1") (pintype "power_in"))
    )
    (net (code "64") (name "Net-(U1-VDDA)") (class "Default")
      (node (ref "C9") (pin "2") (pinfunction "2_2") (pintype "passive"))
      (node (ref "R7") (pin "2") (pinfunction "2_2") (pintype "passive"))
      (node (ref "U1") (pin "9") (pinfunction "VDDA_9") (pintype "power_in"))
    )
    (net (code "65") (name "USB_5V") (class "Default")
      (node (ref "F2") (pin "1") (pinfunction "1_1") (pintype "passive"))
      (node (ref "S1") (pin "2") (pinfunction "2_2") (pintype "passive"))
    )
    (net (code "66") (name "USB_5V_Core") (class "Default")
      (node (ref "J2") (pin "1") (pinfunction "P1_1") (pintype "passive"))
      (node (ref "J3") (pin "1") (pinfunction "P1_1") (pintype "passive"))
      (node (ref "S1") (pin "1") (pinfunction "1_1") (pintype "passive"))
    )
    (net (code "67") (name "USB_5V_Expansion") (class "Default")
      (node (ref "J4") (pin "1") (pinfunction "VCC_1") (pintype "passive"))
      (node (ref "J4") (pin "3") (pinfunction "VCC_3") (pintype "passive"))
      (node (ref "J4") (pin "5") (pinfunction "VCC_5") (pintype "passive"))
      (node (ref "J4") (pin "7") (pinfunction "VCC_7") (pintype "passive"))
      (node (ref "J4") (pin "9") (pinfunction "VCC_9") (pintype "passive"))
      (node (ref "S1") (pin "3") (pinfunction "3_3") (pintype "passive"))
    )
    (net (code "68") (name "unconnected-(IC1-CTS#-Pad9)") (class "Default")
      (node (ref "IC1") (pin "9") (pinfunction "CTS#_9") (pintype "passive+no_connect"))
    )
    (net (code "69") (name "unconnected-(IC1-DCD#-Pad12)") (class "Default")
      (node (ref "IC1") (pin "12") (pinfunction "DCD#_12") (pintype "passive+no_connect"))
    )
    (net (code "70") (name "unconnected-(IC1-DSR#-Pad10)") (class "Default")
      (node (ref "IC1") (pin "10") (pinfunction "DSR#_10") (pintype "passive+no_connect"))
    )
    (net (code "71") (name "unconnected-(IC1-RI#-Pad11)") (class "Default")
      (node (ref "IC1") (pin "11") (pinfunction "RI#_11") (pintype "passive+no_connect"))
    )
    (net (code "72") (name "unconnected-(IC1-RS232-Pad15)") (class "Default")
      (node (ref "IC1") (pin "15") (pinfunction "RS232_15") (pintype "passive+no_connect"))
    )
    (net (code "73") (name "unconnected-(J2-P4-Pad4)") (class "Default")
      (node (ref "J2") (pin "4") (pinfunction "P4_4") (pintype "passive+no_connect"))
    )
    (net (code "74") (name "unconnected-(J3-P4-Pad4)") (class "Default")
      (node (ref "J3") (pin "4") (pinfunction "P4_4") (pintype "passive+no_connect"))
    )
    (net (code "75") (name "unconnected-(J4-Pad10)") (class "Default")
      (node (ref "J4") (pin "10") (pinfunction "10_10") (pintype "passive"))
    )
    (net (code "76") (name "unconnected-(J4-Pad11)") (class "Default")
      (node (ref "J4") (pin "11") (pinfunction "11_11") (pintype "passive"))
    )
    (net (code "77") (name "unconnected-(J4-Pad13)") (class "Default")
      (node (ref "J4") (pin "13") (pinfunction "13_13") (pintype "passive"))
    )
    (net (code "78") (name "unconnected-(J4-Pad15)") (class "Default")
      (node (ref "J4") (pin "15") (pinfunction "15_15") (pintype "passive"))
    )
    (net (code "79") (name "unconnected-(J4-Pad17)") (class "Default")
      (node (ref "J4") (pin "17") (pinfunction "17_17") (pintype "passive"))
    )
    (net (code "80") (name "unconnected-(J4-Pad19)") (class "Default")
      (node (ref "J4") (pin "19") (pinfunction "19_19") (pintype "passive"))
    )
    (net (code "81") (name "unconnected-(J4-Pad21)") (class "Default")
      (node (ref "J4") (pin "21") (pinfunction "21_21") (pintype "passive"))
    )
    (net (code "82") (name "unconnected-(J4-Pad23)") (class "Default")
      (node (ref "J4") (pin "23") (pinfunction "23_23") (pintype "passive"))
    )
    (net (code "83") (name "unconnected-(J4-Pad25)") (class "Default")
      (node (ref "J4") (pin "25") (pinfunction "25_25") (pintype "passive"))
    )
    (net (code "84") (name "unconnected-(J4-Pad27)") (class "Default")
      (node (ref "J4") (pin "27") (pinfunction "27_27") (pintype "passive"))
    )
    (net (code "85") (name "unconnected-(J4-Pad29)") (class "Default")
      (node (ref "J4") (pin "29") (pinfunction "29_29") (pintype "passive"))
    )
    (net (code "86") (name "unconnected-(J4-Pad30)") (class "Default")
      (node (ref "J4") (pin "30") (pinfunction "30_30") (pintype "passive"))
    )
    (net (code "87") (name "unconnected-(J4-Pad31)") (class "Default")
      (node (ref "J4") (pin "31") (pinfunction "31_31") (pintype "passive"))
    )
    (net (code "88") (name "unconnected-(J4-Pad32)") (class "Default")
      (node (ref "J4") (pin "32") (pinfunction "32_32") (pintype "passive"))
    )
    (net (code "89") (name "unconnected-(J4-Pad33)") (class "Default")
      (node (ref "J4") (pin "33") (pinfunction "33_33") (pintype "passive"))
    )
    (net (code "90") (name "unconnected-(J4-Pad35)") (class "Default")
      (node (ref "J4") (pin "35") (pinfunction "35_35") (pintype "passive"))
    )
    (net (code "91") (name "unconnected-(J4-Pad37)") (class "Default")
      (node (ref "J4") (pin "37") (pinfunction "37_37") (pintype "passive"))
    )
    (net (code "92") (name "unconnected-(J4-Pad39)") (class "Default")
      (node (ref "J4") (pin "39") (pinfunction "39_39") (pintype "passive"))
    )
    (net (code "93") (name "unconnected-(J4-Pad41)") (class "Default")
      (node (ref "J4") (pin "41") (pinfunction "41_41") (pintype "passive"))
    )
    (net (code "94") (name "unconnected-(J4-Pad43)") (class "Default")
      (node (ref "J4") (pin "43") (pinfunction "43_43") (pintype "passive"))
    )
    (net (code "95") (name "unconnected-(J4-Pad45)") (class "Default")
      (node (ref "J4") (pin "45") (pinfunction "45_45") (pintype "passive"))
    )
    (net (code "96") (name "unconnected-(J4-Pad47)") (class "Default")
      (node (ref "J4") (pin "47") (pinfunction "47_47") (pintype "passive"))
    )
    (net (code "97") (name "unconnected-(J4-Pad49)") (class "Default")
      (node (ref "J4") (pin "49") (pinfunction "49_49") (pintype "passive"))
    )
    (net (code "98") (name "unconnected-(J4-Pad51)") (class "Default")
      (node (ref "J4") (pin "51") (pinfunction "51_51") (pintype "passive"))
    )
    (net (code "99") (name "unconnected-(J4-Pad53)") (class "Default")
      (node (ref "J4") (pin "53") (pinfunction "53_53") (pintype "passive"))
    )
    (net (code "100") (name "unconnected-(J4-Pad55)") (class "Default")
      (node (ref "J4") (pin "55") (pinfunction "55_55") (pintype "passive"))
    )
    (net (code "101") (name "unconnected-(J4-Pad56)") (class "Default")
      (node (ref "J4") (pin "56") (pinfunction "56_56") (pintype "passive"))
    )
    (net (code "102") (name "unconnected-(J4-Pad57)") (class "Default")
      (node (ref "J4") (pin "57") (pinfunction "57_57") (pintype "passive"))
    )
    (net (code "103") (name "unconnected-(J4-Pad58)") (class "Default")
      (node (ref "J4") (pin "58") (pinfunction "58_58") (pintype "passive"))
    )
    (net (code "104") (name "unconnected-(J4-Pad59)") (class "Default")
      (node (ref "J4") (pin "59") (pinfunction "59_59") (pintype "passive"))
    )
    (net (code "105") (name "unconnected-(J4-Pad60)") (class "Default")
      (node (ref "J4") (pin "60") (pinfunction "60_60") (pintype "passive"))
    )
    (net (code "106") (name "unconnected-(J4-Pad61)") (class "Default")
      (node (ref "J4") (pin "61") (pinfunction "61_61") (pintype "passive"))
    )
    (net (code "107") (name "unconnected-(J4-Pad62)") (class "Default")
      (node (ref "J4") (pin "62") (pinfunction "62_62") (pintype "passive"))
    )
    (net (code "108") (name "unconnected-(J4-Pad63)") (class "Default")
      (node (ref "J4") (pin "63") (pinfunction "63_63") (pintype "passive"))
    )
    (net (code "109") (name "unconnected-(J4-Pad64)") (class "Default")
      (node (ref "J4") (pin "64") (pinfunction "64_64") (pintype "passive"))
    )
    (net (code "110") (name "unconnected-(J4-Pad65)") (class "Default")
      (node (ref "J4") (pin "65") (pinfunction "65_65") (pintype "passive"))
    )
    (net (code "111") (name "unconnected-(J4-Pad66)") (class "Default")
      (node (ref "J4") (pin "66") (pinfunction "66_66") (pintype "passive"))
    )
    (net (code "112") (name "unconnected-(J4-Pad67)") (class "Default")
      (node (ref "J4") (pin "67") (pinfunction "67_67") (pintype "passive"))
    )
  )
)
